# shcematics.net
KiCad netlist of a schematic drawn in Altium Designer
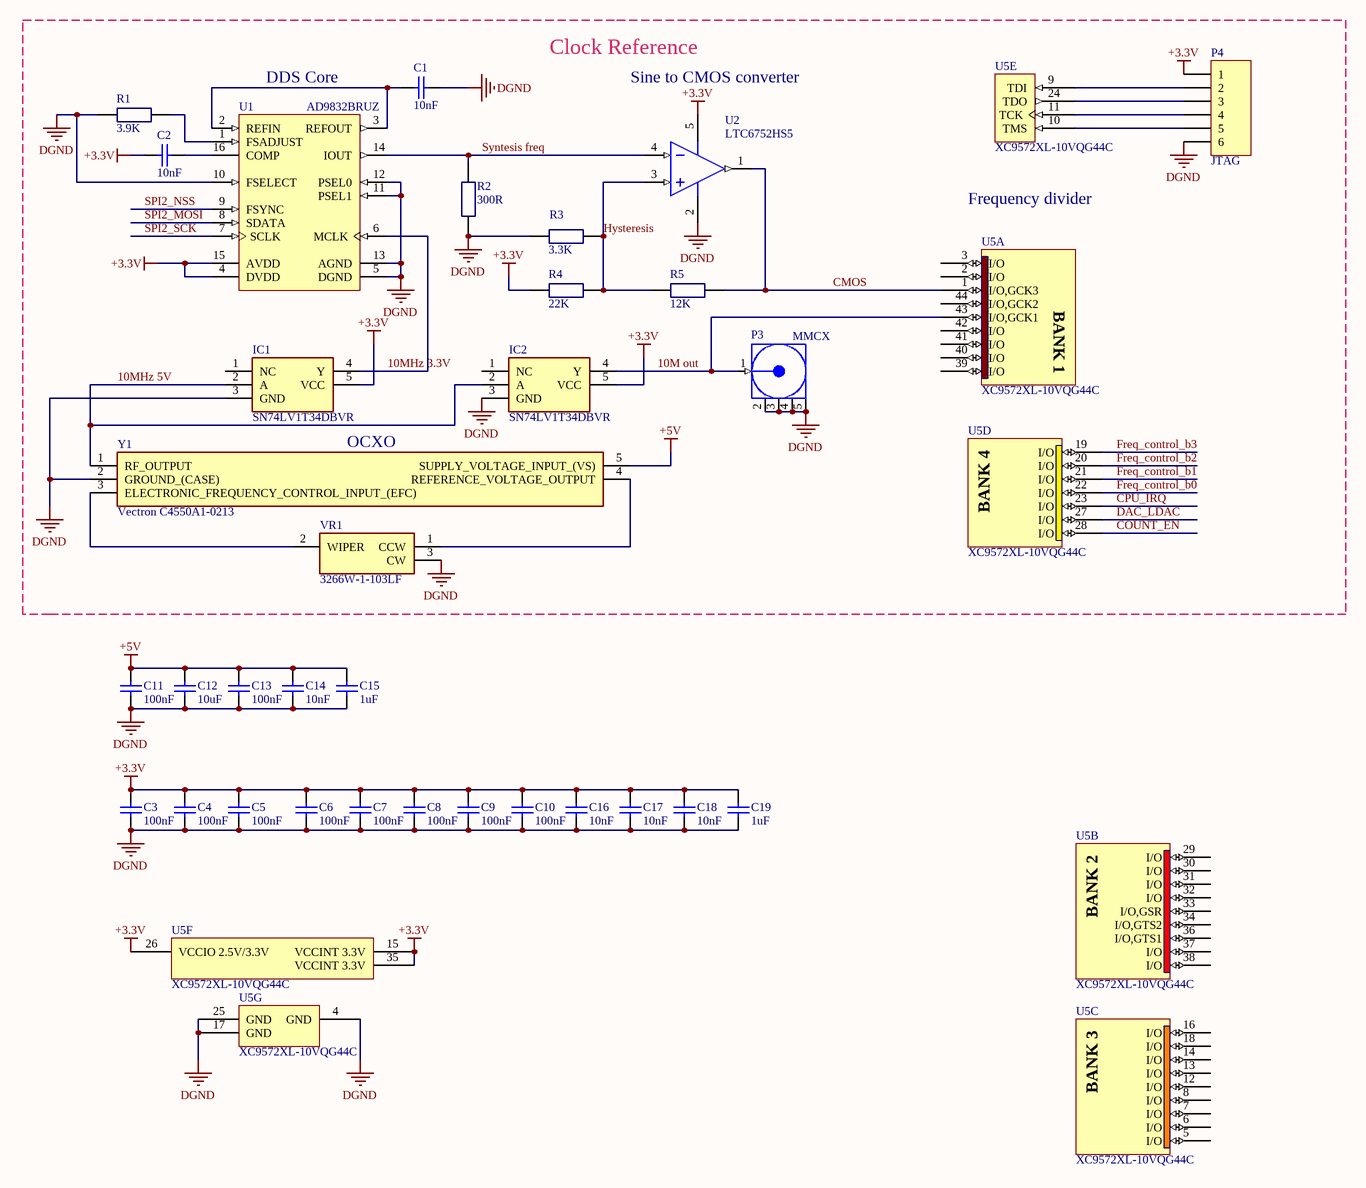
[diagram p0: shcematics.SchDoc]

(export (version "E")
  (design (tool "Eeschema 10.0.6"))
  (components
    (comp (ref "C1")
      (value "10nF")
      (footprint "CAP 0603")
      (description "Capacitor (Semiconductor SIM Model)")
      (fields (field (name "PUBLISHER") "Altium Limited"))
      (libsource (lib "Miscellaneous Devices") (part "Cap Semi"))
    )
    (comp (ref "C2")
      (value "10nF")
      (footprint "CAP 0603")
      (description "Capacitor (Semiconductor SIM Model)")
      (fields (field (name "PUBLISHER") "Altium Limited"))
      (libsource (lib "Miscellaneous Devices") (part "Cap Semi"))
    )
    (comp (ref "C3")
      (value "100nF")
      (footprint "CAP 0603")
      (description "Capacitor (Semiconductor SIM Model)")
      (fields (field (name "PUBLISHER") "Altium Limited"))
      (libsource (lib "Miscellaneous Devices") (part "Cap Semi"))
    )
    (comp (ref "C4")
      (value "100nF")
      (footprint "CAP 0603")
      (description "Capacitor (Semiconductor SIM Model)")
      (fields (field (name "PUBLISHER") "Altium Limited"))
      (libsource (lib "Miscellaneous Devices") (part "Cap Semi"))
    )
    (comp (ref "C5")
      (value "100nF")
      (footprint "CAP 0603")
      (description "Capacitor (Semiconductor SIM Model)")
      (fields (field (name "PUBLISHER") "Altium Limited"))
      (libsource (lib "Miscellaneous Devices") (part "Cap Semi"))
    )
    (comp (ref "C6")
      (value "100nF")
      (footprint "CAP 0603")
      (description "Capacitor (Semiconductor SIM Model)")
      (fields (field (name "PUBLISHER") "Altium Limited"))
      (libsource (lib "Miscellaneous Devices") (part "Cap Semi"))
    )
    (comp (ref "C7")
      (value "100nF")
      (footprint "CAP 0603")
      (description "Capacitor (Semiconductor SIM Model)")
      (fields (field (name "PUBLISHER") "Altium Limited"))
      (libsource (lib "Miscellaneous Devices") (part "Cap Semi"))
    )
    (comp (ref "C8")
      (value "100nF")
      (footprint "CAP 0603")
      (description "Capacitor (Semiconductor SIM Model)")
      (fields (field (name "PUBLISHER") "Altium Limited"))
      (libsource (lib "Miscellaneous Devices") (part "Cap Semi"))
    )
    (comp (ref "C9")
      (value "100nF")
      (footprint "CAP 0603")
      (description "Capacitor (Semiconductor SIM Model)")
      (fields (field (name "PUBLISHER") "Altium Limited"))
      (libsource (lib "Miscellaneous Devices") (part "Cap Semi"))
    )
    (comp (ref "C10")
      (value "100nF")
      (footprint "CAP 0603")
      (description "Capacitor (Semiconductor SIM Model)")
      (fields (field (name "PUBLISHER") "Altium Limited"))
      (libsource (lib "Miscellaneous Devices") (part "Cap Semi"))
    )
    (comp (ref "C11")
      (value "100nF")
      (footprint "CAP 0603")
      (description "Capacitor (Semiconductor SIM Model)")
      (fields (field (name "PUBLISHER") "Altium Limited"))
      (libsource (lib "Miscellaneous Devices") (part "Cap Semi"))
    )
    (comp (ref "C12")
      (value "10uF")
      (footprint "CAP 0603")
      (description "Capacitor (Semiconductor SIM Model)")
      (fields (field (name "PUBLISHER") "Altium Limited"))
      (libsource (lib "Miscellaneous Devices") (part "Cap Semi"))
    )
    (comp (ref "C13")
      (value "100nF")
      (footprint "CAP 0603")
      (description "Capacitor (Semiconductor SIM Model)")
      (fields (field (name "PUBLISHER") "Altium Limited"))
      (libsource (lib "Miscellaneous Devices") (part "Cap Semi"))
    )
    (comp (ref "C14")
      (value "10nF")
      (footprint "CAP 0603")
      (description "Capacitor (Semiconductor SIM Model)")
      (fields (field (name "PUBLISHER") "Altium Limited"))
      (libsource (lib "Miscellaneous Devices") (part "Cap Semi"))
    )
    (comp (ref "C15")
      (value "1uF")
      (footprint "CAP 0603")
      (description "Capacitor (Semiconductor SIM Model)")
      (fields (field (name "PUBLISHER") "Altium Limited"))
      (libsource (lib "Miscellaneous Devices") (part "Cap Semi"))
    )
    (comp (ref "C16")
      (value "10nF")
      (footprint "CAP 0603")
      (description "Capacitor (Semiconductor SIM Model)")
      (fields (field (name "PUBLISHER") "Altium Limited"))
      (libsource (lib "Miscellaneous Devices") (part "Cap Semi"))
    )
    (comp (ref "C17")
      (value "10nF")
      (footprint "CAP 0603")
      (description "Capacitor (Semiconductor SIM Model)")
      (fields (field (name "PUBLISHER") "Altium Limited"))
      (libsource (lib "Miscellaneous Devices") (part "Cap Semi"))
    )
    (comp (ref "C18")
      (value "10nF")
      (footprint "CAP 0603")
      (description "Capacitor (Semiconductor SIM Model)")
      (fields (field (name "PUBLISHER") "Altium Limited"))
      (libsource (lib "Miscellaneous Devices") (part "Cap Semi"))
    )
    (comp (ref "C19")
      (value "1uF")
      (footprint "CAP 0603")
      (description "Capacitor (Semiconductor SIM Model)")
      (fields (field (name "PUBLISHER") "Altium Limited"))
      (libsource (lib "Miscellaneous Devices") (part "Cap Semi"))
    )
    (comp (ref "IC1")
      (value "SN74LV1T34DBVR")
      (footprint "SamacSys:SOT95P280X145-5N")
      (description "Integrated Circuit")
      (fields (field (name "MOUSER PART NUMBER") "595-SN74LV1T34DBVR"))
      (libsource (lib "*") (part "SN74LV1T34DBVR"))
    )
    (comp (ref "IC2")
      (value "SN74LV1T34DBVR")
      (footprint "SamacSys:SOT95P280X145-5N")
      (description "Integrated Circuit")
      (fields (field (name "MOUSER PART NUMBER") "595-SN74LV1T34DBVR"))
      (libsource (lib "*") (part "SN74LV1T34DBVR"))
    )
    (comp (ref "P3")
      (value "MMCX")
      (footprint "MMCX2.54-V5")
      (description "RF Coaxial PCB Connector, MMCX; Thru-Hole, Vertical Mount Plug,  50 Ohm Impedance")
      (fields (field (name "PUBLISHER") "Altium Limited"))
      (libsource (lib "Miscellaneous Connectors") (part "COAX-M"))
    )
    (comp (ref "P4")
      (value "JTAG")
      (footprint "HDR1X6")
      (description "Header, 6-Pin")
      (fields (field (name "PUBLISHER") "Altium Limited"))
      (libsource (lib "Miscellaneous Connectors") (part "Header 6"))
    )
    (comp (ref "R1")
      (value "3.9K")
      (footprint "1608[0603]")
      (libsource (lib "Микрон-3") (part "Resistor 0805"))
    )
    (comp (ref "R2")
      (value "300R")
      (footprint "Yegeo 0603")
      (libsource (lib "Микрон-3") (part "Resistor 0805"))
    )
    (comp (ref "R3")
      (value "3.3K")
      (footprint "Yegeo 0603")
      (libsource (lib "Микрон-3") (part "Resistor 0805"))
    )
    (comp (ref "R4")
      (value "22K")
      (footprint "Yegeo 0603")
      (libsource (lib "Микрон-3") (part "Resistor 0805"))
    )
    (comp (ref "R5")
      (value "12K")
      (footprint "Yegeo 0603")
      (libsource (lib "Микрон-3") (part "Resistor 0805"))
    )
    (comp (ref "U1")
      (value "AD9832BRUZ")
      (footprint "ADI-RU-16_N")
      (description "25 MHz Direct Digital Synthesizer, Waveform Generator, 10-Bit, Serial, RU-16, 96 Tube, Pb-Free")
      (libsource (lib "Ramp-generator") (part "AD9832BRUZ"))
    )
    (comp (ref "U2")
      (value "LTC6752HS5")
      (footprint "TI-DBV5_N")
      (fields (field (name "MANUFACTURER") "Texas Instruments") (field (name "PARTNUMBER") "OPA353NA/250"))
      (libsource (lib "TI Amplifiers and Linear Operational Amplifier Precision Amplifier Part One") (part "OPA353NA/250"))
    )
    (comp (ref "U5")
      (value "XC9572XL-10VQG44C")
      (footprint "VQG44_N")
      (fields (field (name "PUBLISHER") "Altium Limited"))
      (libsource (lib "Xilinx XC9500XL") (part "XC9572XL-10VQG44C"))
    )
    (comp (ref "VR1")
      (value "3266W-1-103LF")
      (footprint "SamacSys:3266W")
      (description "Variable Resistor")
      (fields (field (name "MOUSER PART NUMBER") "652-3266W-1-103LF"))
      (libsource (lib "*") (part "3266W-1-103LF"))
    )
    (comp (ref "Y1")
      (value "Vectron C4550A1-0213")
      (footprint "SamacSys:C4550C508SV120RFSA11128MHZ")
      (description "Crystal or Oscillator")
      (libsource (lib "SamacSys") (part "C4550C508SV120RFSA1112.8MHZ"))
    )
  )
  (nets
    (net (code "1") (name "+3.3V") (class "Default")
      (node (ref "C10") (pin "2") (pinfunction "2_2") (pintype "passive"))
      (node (ref "C16") (pin "2") (pinfunction "2_2") (pintype "passive"))
      (node (ref "C17") (pin "2") (pinfunction "2_2") (pintype "passive"))
      (node (ref "C18") (pin "2") (pinfunction "2_2") (pintype "passive"))
      (node (ref "C19") (pin "2") (pinfunction "2_2") (pintype "passive"))
      (node (ref "C2") (pin "1") (pinfunction "1_1") (pintype "passive"))
      (node (ref "C3") (pin "2") (pinfunction "2_2") (pintype "passive"))
      (node (ref "C4") (pin "2") (pinfunction "2_2") (pintype "passive"))
      (node (ref "C5") (pin "2") (pinfunction "2_2") (pintype "passive"))
      (node (ref "C6") (pin "2") (pinfunction "2_2") (pintype "passive"))
      (node (ref "C7") (pin "2") (pinfunction "2_2") (pintype "passive"))
      (node (ref "C8") (pin "2") (pinfunction "2_2") (pintype "passive"))
      (node (ref "C9") (pin "2") (pinfunction "2_2") (pintype "passive"))
      (node (ref "IC1") (pin "5") (pinfunction "VCC_5") (pintype "passive"))
      (node (ref "IC2") (pin "5") (pinfunction "VCC_5") (pintype "passive"))
      (node (ref "P4") (pin "1") (pinfunction "1_1") (pintype "passive"))
      (node (ref "R4") (pin "2") (pinfunction "2_2") (pintype "passive"))
      (node (ref "U1") (pin "15") (pinfunction "AVDD_15") (pintype "power_in"))
      (node (ref "U1") (pin "4") (pinfunction "DVDD_4") (pintype "power_in"))
      (node (ref "U2") (pin "5") (pinfunction "V+_5") (pintype "power_in"))
      (node (ref "U5") (pin "15") (pinfunction "VCCINT_3.3V_15") (pintype "power_in"))
      (node (ref "U5") (pin "26") (pinfunction "VCCIO_2.5V/3.3V_26") (pintype "power_in"))
      (node (ref "U5") (pin "35") (pinfunction "VCCINT_3.3V_35") (pintype "power_in"))
    )
    (net (code "2") (name "+5V") (class "Default")
      (node (ref "C11") (pin "2") (pinfunction "2_2") (pintype "passive"))
      (node (ref "C12") (pin "2") (pinfunction "2_2") (pintype "passive"))
      (node (ref "C13") (pin "2") (pinfunction "2_2") (pintype "passive"))
      (node (ref "C14") (pin "2") (pinfunction "2_2") (pintype "passive"))
      (node (ref "C15") (pin "2") (pinfunction "2_2") (pintype "passive"))
      (node (ref "Y1") (pin "5") (pinfunction "SUPPLY_VOLTAGE_INPUT_(VS)_5") (pintype "passive"))
    )
    (net (code "3") (name "/10M out") (class "Default")
      (node (ref "IC2") (pin "4") (pinfunction "Y_4") (pintype "passive"))
      (node (ref "P3") (pin "1") (pinfunction "Signal_1") (pintype "input"))
      (node (ref "U5") (pin "43") (pinfunction "I/O,GCK1_43") (pintype "bidirectional"))
    )
    (net (code "4") (name "/10MHz 3.3V") (class "Default")
      (node (ref "IC1") (pin "4") (pinfunction "Y_4") (pintype "passive"))
      (node (ref "U1") (pin "6") (pinfunction "MCLK_6") (pintype "input"))
    )
    (net (code "5") (name "/10MHz 5V") (class "Default")
      (node (ref "IC1") (pin "2") (pinfunction "A_2") (pintype "passive"))
      (node (ref "IC2") (pin "2") (pinfunction "A_2") (pintype "passive"))
      (node (ref "Y1") (pin "1") (pinfunction "RF_OUTPUT_1") (pintype "passive"))
    )
    (net (code "6") (name "/CMOS") (class "Default")
      (node (ref "R5") (pin "1") (pinfunction "A_1") (pintype "passive"))
      (node (ref "U2") (pin "1") (pinfunction "OUT_1") (pintype "output"))
      (node (ref "U5") (pin "1") (pinfunction "I/O,GCK3_1") (pintype "bidirectional"))
    )
    (net (code "7") (name "/COUNT_EN") (class "Default")
      (node (ref "U5") (pin "28") (pinfunction "I/O_28") (pintype "bidirectional"))
    )
    (net (code "8") (name "/CPU_IRQ") (class "Default")
      (node (ref "U5") (pin "23") (pinfunction "I/O_23") (pintype "bidirectional"))
    )
    (net (code "9") (name "/DAC_LDAC") (class "Default")
      (node (ref "U5") (pin "27") (pinfunction "I/O_27") (pintype "bidirectional"))
    )
    (net (code "10") (name "/Freq_control_b0") (class "Default")
      (node (ref "U5") (pin "22") (pinfunction "I/O_22") (pintype "bidirectional"))
    )
    (net (code "11") (name "/Freq_control_b1") (class "Default")
      (node (ref "U5") (pin "21") (pinfunction "I/O_21") (pintype "bidirectional"))
    )
    (net (code "12") (name "/Freq_control_b2") (class "Default")
      (node (ref "U5") (pin "20") (pinfunction "I/O_20") (pintype "bidirectional"))
    )
    (net (code "13") (name "/Freq_control_b3") (class "Default")
      (node (ref "U5") (pin "19") (pinfunction "I/O_19") (pintype "bidirectional"))
    )
    (net (code "14") (name "/Hysteresis") (class "Default")
      (node (ref "R3") (pin "1") (pinfunction "A_1") (pintype "passive"))
      (node (ref "R4") (pin "1") (pinfunction "A_1") (pintype "passive"))
      (node (ref "R5") (pin "2") (pinfunction "2_2") (pintype "passive"))
      (node (ref "U2") (pin "3") (pinfunction "IN+_3") (pintype "input"))
    )
    (net (code "15") (name "/SPI2_MOSI") (class "Default")
      (node (ref "U1") (pin "8") (pinfunction "SDATA_8") (pintype "input"))
    )
    (net (code "16") (name "/SPI2_NSS") (class "Default")
      (node (ref "U1") (pin "9") (pinfunction "FSYNC_9") (pintype "input"))
    )
    (net (code "17") (name "/SPI2_SCK") (class "Default")
      (node (ref "U1") (pin "7") (pinfunction "SCLK_7") (pintype "input"))
    )
    (net (code "18") (name "/Syntesis freq") (class "Default")
      (node (ref "R2") (pin "2") (pinfunction "2_2") (pintype "passive"))
      (node (ref "U1") (pin "14") (pinfunction "IOUT_14") (pintype "output"))
      (node (ref "U2") (pin "4") (pinfunction "IN-_4") (pintype "input"))
    )
    (net (code "19") (name "DGND") (class "Default")
      (node (ref "C1") (pin "2") (pinfunction "2_2") (pintype "passive"))
      (node (ref "C10") (pin "1") (pinfunction "1_1") (pintype "passive"))
      (node (ref "C11") (pin "1") (pinfunction "1_1") (pintype "passive"))
      (node (ref "C12") (pin "1") (pinfunction "1_1") (pintype "passive"))
      (node (ref "C13") (pin "1") (pinfunction "1_1") (pintype "passive"))
      (node (ref "C14") (pin "1") (pinfunction "1_1") (pintype "passive"))
      (node (ref "C15") (pin "1") (pinfunction "1_1") (pintype "passive"))
      (node (ref "C16") (pin "1") (pinfunction "1_1") (pintype "passive"))
      (node (ref "C17") (pin "1") (pinfunction "1_1") (pintype "passive"))
      (node (ref "C18") (pin "1") (pinfunction "1_1") (pintype "passive"))
      (node (ref "C19") (pin "1") (pinfunction "1_1") (pintype "passive"))
      (node (ref "C3") (pin "1") (pinfunction "1_1") (pintype "passive"))
      (node (ref "C4") (pin "1") (pinfunction "1_1") (pintype "passive"))
      (node (ref "C5") (pin "1") (pinfunction "1_1") (pintype "passive"))
      (node (ref "C6") (pin "1") (pinfunction "1_1") (pintype "passive"))
      (node (ref "C7") (pin "1") (pinfunction "1_1") (pintype "passive"))
      (node (ref "C8") (pin "1") (pinfunction "1_1") (pintype "passive"))
      (node (ref "C9") (pin "1") (pinfunction "1_1") (pintype "passive"))
      (node (ref "IC1") (pin "3") (pinfunction "GND_3") (pintype "passive"))
      (node (ref "IC2") (pin "3") (pinfunction "GND_3") (pintype "passive"))
      (node (ref "P3") (pin "2") (pinfunction "GND_2") (pintype "power_in"))
      (node (ref "P3") (pin "3") (pinfunction "GND_3") (pintype "power_in"))
      (node (ref "P3") (pin "4") (pinfunction "GND_4") (pintype "power_in"))
      (node (ref "P3") (pin "5") (pinfunction "GND_5") (pintype "power_in"))
      (node (ref "P4") (pin "6") (pinfunction "6_6") (pintype "passive"))
      (node (ref "R1") (pin "2") (pinfunction "2_2") (pintype "passive"))
      (node (ref "R2") (pin "1") (pinfunction "A_1") (pintype "passive"))
      (node (ref "R3") (pin "2") (pinfunction "2_2") (pintype "passive"))
      (node (ref "U1") (pin "10") (pinfunction "FSELECT_10") (pintype "input"))
      (node (ref "U1") (pin "11") (pinfunction "PSEL1_11") (pintype "input"))
      (node (ref "U1") (pin "12") (pinfunction "PSEL0_12") (pintype "input"))
      (node (ref "U1") (pin "13") (pinfunction "AGND_13") (pintype "power_in"))
      (node (ref "U1") (pin "5") (pinfunction "DGND_5") (pintype "power_in"))
      (node (ref "U2") (pin "2") (pinfunction "V-_2") (pintype "power_in"))
      (node (ref "U5") (pin "17") (pinfunction "GND_17") (pintype "power_in"))
      (node (ref "U5") (pin "25") (pinfunction "GND_25") (pintype "power_in"))
      (node (ref "U5") (pin "4") (pinfunction "GND_4") (pintype "power_in"))
      (node (ref "VR1") (pin "3") (pinfunction "CW_3") (pintype "passive"))
      (node (ref "Y1") (pin "2") (pinfunction "GROUND_(CASE)_2") (pintype "passive"))
    )
    (net (code "20") (name "Net-(R1-A)") (class "Default")
      (node (ref "R1") (pin "1") (pinfunction "A_1") (pintype "passive"))
      (node (ref "U1") (pin "1") (pinfunction "FSADJUST_1") (pintype "input"))
    )
    (net (code "21") (name "Net-(U1-COMP)") (class "Default")
      (node (ref "C2") (pin "2") (pinfunction "2_2") (pintype "passive"))
      (node (ref "U1") (pin "16") (pinfunction "COMP_16") (pintype "passive"))
    )
    (net (code "22") (name "Net-(U1-REFIN)") (class "Default")
      (node (ref "C1") (pin "1") (pinfunction "1_1") (pintype "passive"))
      (node (ref "U1") (pin "2") (pinfunction "REFIN_2") (pintype "input"))
      (node (ref "U1") (pin "3") (pinfunction "REFOUT_3") (pintype "output"))
    )
    (net (code "23") (name "Net-(U5E-TCK)") (class "Default")
      (node (ref "P4") (pin "4") (pinfunction "4_4") (pintype "passive"))
      (node (ref "U5") (pin "11") (pinfunction "TCK_11") (pintype "input"))
    )
    (net (code "24") (name "Net-(U5E-TDI)") (class "Default")
      (node (ref "P4") (pin "2") (pinfunction "2_2") (pintype "passive"))
      (node (ref "U5") (pin "9") (pinfunction "TDI_9") (pintype "input"))
    )
    (net (code "25") (name "Net-(U5E-TDO)") (class "Default")
      (node (ref "P4") (pin "3") (pinfunction "3_3") (pintype "passive"))
      (node (ref "U5") (pin "24") (pinfunction "TDO_24") (pintype "output"))
    )
    (net (code "26") (name "Net-(U5E-TMS)") (class "Default")
      (node (ref "P4") (pin "5") (pinfunction "5_5") (pintype "passive"))
      (node (ref "U5") (pin "10") (pinfunction "TMS_10") (pintype "input"))
    )
    (net (code "27") (name "Net-(VR1-CCW)") (class "Default")
      (node (ref "VR1") (pin "1") (pinfunction "CCW_1") (pintype "passive"))
      (node (ref "Y1") (pin "4") (pinfunction "REFERENCE_VOLTAGE_OUTPUT_4") (pintype "passive"))
    )
    (net (code "28") (name "Net-(VR1-WIPER)") (class "Default")
      (node (ref "VR1") (pin "2") (pinfunction "WIPER_2") (pintype "passive"))
      (node (ref "Y1") (pin "3") (pinfunction "ELECTRONIC_FREQUENCY_CONTROL_INPUT_(EFC)_3") (pintype "passive"))
    )
    (net (code "29") (name "unconnected-(IC1-NC-Pad1)") (class "Default")
      (node (ref "IC1") (pin "1") (pinfunction "NC_1") (pintype "passive"))
    )
    (net (code "30") (name "unconnected-(IC2-NC-Pad1)") (class "Default")
      (node (ref "IC2") (pin "1") (pinfunction "NC_1") (pintype "passive"))
    )
    (net (code "31") (name "unconnected-(U5A-I{slash}O,GCK2-Pad44)") (class "Default")
      (node (ref "U5") (pin "44") (pinfunction "I/O,GCK2_44") (pintype "bidirectional"))
    )
    (net (code "32") (name "unconnected-(U5A-I{slash}O-Pad2)") (class "Default")
      (node (ref "U5") (pin "2") (pinfunction "I/O_2") (pintype "bidirectional"))
    )
    (net (code "33") (name "unconnected-(U5A-I{slash}O-Pad3)") (class "Default")
      (node (ref "U5") (pin "3") (pinfunction "I/O_3") (pintype "bidirectional"))
    )
    (net (code "34") (name "unconnected-(U5A-I{slash}O-Pad39)") (class "Default")
      (node (ref "U5") (pin "39") (pinfunction "I/O_39") (pintype "bidirectional"))
    )
    (net (code "35") (name "unconnected-(U5A-I{slash}O-Pad40)") (class "Default")
      (node (ref "U5") (pin "40") (pinfunction "I/O_40") (pintype "bidirectional"))
    )
    (net (code "36") (name "unconnected-(U5A-I{slash}O-Pad41)") (class "Default")
      (node (ref "U5") (pin "41") (pinfunction "I/O_41") (pintype "bidirectional"))
    )
    (net (code "37") (name "unconnected-(U5A-I{slash}O-Pad42)") (class "Default")
      (node (ref "U5") (pin "42") (pinfunction "I/O_42") (pintype "bidirectional"))
    )
    (net (code "38") (name "unconnected-(U5B-I{slash}O,GSR-Pad33)") (class "Default")
      (node (ref "U5") (pin "33") (pinfunction "I/O,GSR_33") (pintype "bidirectional"))
    )
    (net (code "39") (name "unconnected-(U5B-I{slash}O,GTS1-Pad36)") (class "Default")
      (node (ref "U5") (pin "36") (pinfunction "I/O,GTS1_36") (pintype "bidirectional"))
    )
    (net (code "40") (name "unconnected-(U5B-I{slash}O,GTS2-Pad34)") (class "Default")
      (node (ref "U5") (pin "34") (pinfunction "I/O,GTS2_34") (pintype "bidirectional"))
    )
    (net (code "41") (name "unconnected-(U5B-I{slash}O-Pad29)") (class "Default")
      (node (ref "U5") (pin "29") (pinfunction "I/O_29") (pintype "bidirectional"))
    )
    (net (code "42") (name "unconnected-(U5B-I{slash}O-Pad30)") (class "Default")
      (node (ref "U5") (pin "30") (pinfunction "I/O_30") (pintype "bidirectional"))
    )
    (net (code "43") (name "unconnected-(U5B-I{slash}O-Pad31)") (class "Default")
      (node (ref "U5") (pin "31") (pinfunction "I/O_31") (pintype "bidirectional"))
    )
    (net (code "44") (name "unconnected-(U5B-I{slash}O-Pad32)") (class "Default")
      (node (ref "U5") (pin "32") (pinfunction "I/O_32") (pintype "bidirectional"))
    )
    (net (code "45") (name "unconnected-(U5B-I{slash}O-Pad37)") (class "Default")
      (node (ref "U5") (pin "37") (pinfunction "I/O_37") (pintype "bidirectional"))
    )
    (net (code "46") (name "unconnected-(U5B-I{slash}O-Pad38)") (class "Default")
      (node (ref "U5") (pin "38") (pinfunction "I/O_38") (pintype "bidirectional"))
    )
    (net (code "47") (name "unconnected-(U5C-I{slash}O-Pad5)") (class "Default")
      (node (ref "U5") (pin "5") (pinfunction "I/O_5") (pintype "bidirectional"))
    )
    (net (code "48") (name "unconnected-(U5C-I{slash}O-Pad6)") (class "Default")
      (node (ref "U5") (pin "6") (pinfunction "I/O_6") (pintype "bidirectional"))
    )
    (net (code "49") (name "unconnected-(U5C-I{slash}O-Pad7)") (class "Default")
      (node (ref "U5") (pin "7") (pinfunction "I/O_7") (pintype "bidirectional"))
    )
    (net (code "50") (name "unconnected-(U5C-I{slash}O-Pad8)") (class "Default")
      (node (ref "U5") (pin "8") (pinfunction "I/O_8") (pintype "bidirectional"))
    )
    (net (code "51") (name "unconnected-(U5C-I{slash}O-Pad12)") (class "Default")
      (node (ref "U5") (pin "12") (pinfunction "I/O_12") (pintype "bidirectional"))
    )
    (net (code "52") (name "unconnected-(U5C-I{slash}O-Pad13)") (class "Default")
      (node (ref "U5") (pin "13") (pinfunction "I/O_13") (pintype "bidirectional"))
    )
    (net (code "53") (name "unconnected-(U5C-I{slash}O-Pad14)") (class "Default")
      (node (ref "U5") (pin "14") (pinfunction "I/O_14") (pintype "bidirectional"))
    )
    (net (code "54") (name "unconnected-(U5C-I{slash}O-Pad16)") (class "Default")
      (node (ref "U5") (pin "16") (pinfunction "I/O_16") (pintype "bidirectional"))
    )
    (net (code "55") (name "unconnected-(U5C-I{slash}O-Pad18)") (class "Default")
      (node (ref "U5") (pin "18") (pinfunction "I/O_18") (pintype "bidirectional"))
    )
  )
)
